# ADC_part3.net
KiCad netlist of a schematic drawn in Altium Designer
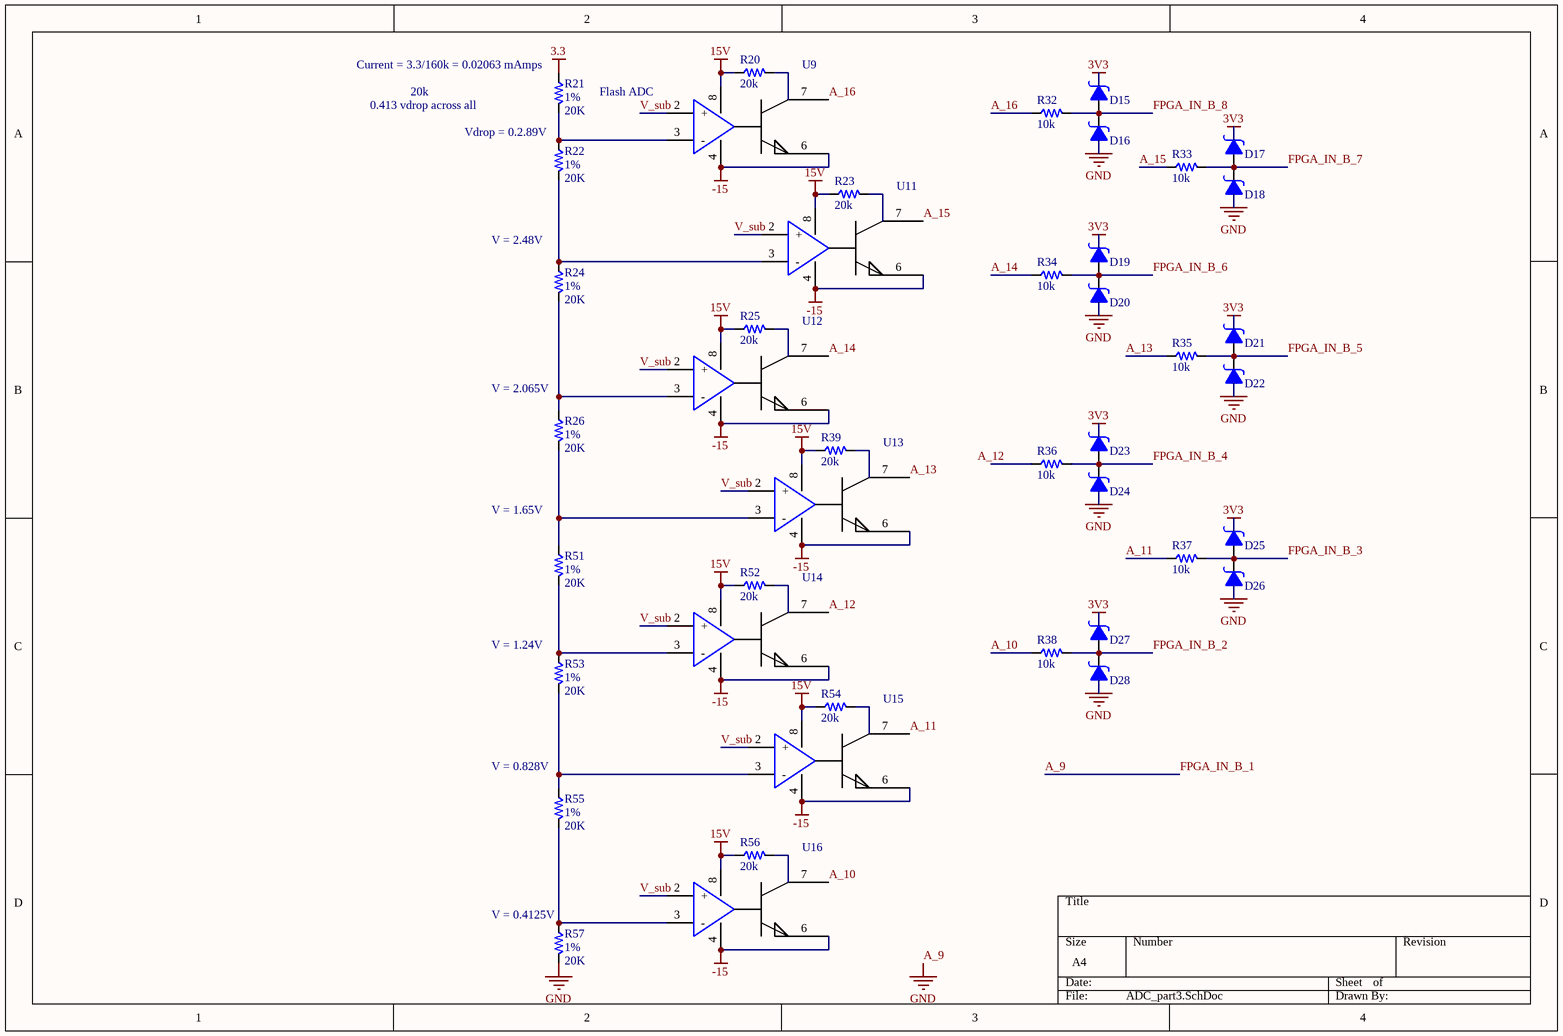
[diagram p0: ADC_part3.SchDoc]

(export (version "E")
  (design (tool "Eeschema 10.0.6"))
  (components
    (comp (ref "D15")
      (value "ONSEMI_MBRM110LT1G")
      (footprint "ON Semi Schottky Diode - MBRM110LT1G")
      (description "DIODE SCHOTTKY 10V 1A")
      (libsource (lib "ON Semi Schottky Diode") (part "ONSEMI_MBRM110LT1G"))
    )
    (comp (ref "D16")
      (value "ONSEMI_MBRM110LT1G")
      (footprint "ON Semi Schottky Diode - MBRM110LT1G")
      (description "DIODE SCHOTTKY 10V 1A")
      (libsource (lib "ON Semi Schottky Diode") (part "ONSEMI_MBRM110LT1G"))
    )
    (comp (ref "D17")
      (value "ONSEMI_MBRM110LT1G")
      (footprint "ON Semi Schottky Diode - MBRM110LT1G")
      (description "DIODE SCHOTTKY 10V 1A")
      (libsource (lib "ON Semi Schottky Diode") (part "ONSEMI_MBRM110LT1G"))
    )
    (comp (ref "D18")
      (value "ONSEMI_MBRM110LT1G")
      (footprint "ON Semi Schottky Diode - MBRM110LT1G")
      (description "DIODE SCHOTTKY 10V 1A")
      (libsource (lib "ON Semi Schottky Diode") (part "ONSEMI_MBRM110LT1G"))
    )
    (comp (ref "D19")
      (value "ONSEMI_MBRM110LT1G")
      (footprint "ON Semi Schottky Diode - MBRM110LT1G")
      (description "DIODE SCHOTTKY 10V 1A")
      (libsource (lib "ON Semi Schottky Diode") (part "ONSEMI_MBRM110LT1G"))
    )
    (comp (ref "D20")
      (value "ONSEMI_MBRM110LT1G")
      (footprint "ON Semi Schottky Diode - MBRM110LT1G")
      (description "DIODE SCHOTTKY 10V 1A")
      (libsource (lib "ON Semi Schottky Diode") (part "ONSEMI_MBRM110LT1G"))
    )
    (comp (ref "D21")
      (value "ONSEMI_MBRM110LT1G")
      (footprint "ON Semi Schottky Diode - MBRM110LT1G")
      (description "DIODE SCHOTTKY 10V 1A")
      (libsource (lib "ON Semi Schottky Diode") (part "ONSEMI_MBRM110LT1G"))
    )
    (comp (ref "D22")
      (value "ONSEMI_MBRM110LT1G")
      (footprint "ON Semi Schottky Diode - MBRM110LT1G")
      (description "DIODE SCHOTTKY 10V 1A")
      (libsource (lib "ON Semi Schottky Diode") (part "ONSEMI_MBRM110LT1G"))
    )
    (comp (ref "D23")
      (value "ONSEMI_MBRM110LT1G")
      (footprint "ON Semi Schottky Diode - MBRM110LT1G")
      (description "DIODE SCHOTTKY 10V 1A")
      (libsource (lib "ON Semi Schottky Diode") (part "ONSEMI_MBRM110LT1G"))
    )
    (comp (ref "D24")
      (value "ONSEMI_MBRM110LT1G")
      (footprint "ON Semi Schottky Diode - MBRM110LT1G")
      (description "DIODE SCHOTTKY 10V 1A")
      (libsource (lib "ON Semi Schottky Diode") (part "ONSEMI_MBRM110LT1G"))
    )
    (comp (ref "D25")
      (value "ONSEMI_MBRM110LT1G")
      (footprint "ON Semi Schottky Diode - MBRM110LT1G")
      (description "DIODE SCHOTTKY 10V 1A")
      (libsource (lib "ON Semi Schottky Diode") (part "ONSEMI_MBRM110LT1G"))
    )
    (comp (ref "D26")
      (value "ONSEMI_MBRM110LT1G")
      (footprint "ON Semi Schottky Diode - MBRM110LT1G")
      (description "DIODE SCHOTTKY 10V 1A")
      (libsource (lib "ON Semi Schottky Diode") (part "ONSEMI_MBRM110LT1G"))
    )
    (comp (ref "D27")
      (value "ONSEMI_MBRM110LT1G")
      (footprint "ON Semi Schottky Diode - MBRM110LT1G")
      (description "DIODE SCHOTTKY 10V 1A")
      (libsource (lib "ON Semi Schottky Diode") (part "ONSEMI_MBRM110LT1G"))
    )
    (comp (ref "D28")
      (value "ONSEMI_MBRM110LT1G")
      (footprint "ON Semi Schottky Diode - MBRM110LT1G")
      (description "DIODE SCHOTTKY 10V 1A")
      (libsource (lib "ON Semi Schottky Diode") (part "ONSEMI_MBRM110LT1G"))
    )
    (comp (ref "R20")
      (value "20k")
      (footprint "PCB_GENERIC_SMD_0603")
      (description "RES 0603 100ohm 5% 63mW")
      (fields (field (name "TOLERANCE") "5%") (field (name "POWER") "63mW"))
      (libsource (lib "RES") (part "R060-00101-05"))
    )
    (comp (ref "R21")
      (value "20K")
      (footprint "PCB_GENERIC_SMD_0603")
      (description "RES 0603 10K 1% 100mW")
      (fields
        (field (name "POWER") "100mW")
        (field (name "TOLERANCE") "1%")
        (field (name "Comment") "R060-00103-01")
      )
      (libsource (lib "RES") (part "R060-00103-01"))
    )
    (comp (ref "R22")
      (value "20K")
      (footprint "PCB_GENERIC_SMD_0603")
      (description "RES 0603 10K 1% 100mW")
      (fields
        (field (name "POWER") "100mW")
        (field (name "TOLERANCE") "1%")
        (field (name "Comment") "R060-00103-01")
      )
      (libsource (lib "RES") (part "R060-00103-01"))
    )
    (comp (ref "R23")
      (value "20k")
      (footprint "PCB_GENERIC_SMD_0603")
      (description "RES 0603 100ohm 5% 63mW")
      (fields (field (name "TOLERANCE") "5%") (field (name "POWER") "63mW"))
      (libsource (lib "RES") (part "R060-00101-05"))
    )
    (comp (ref "R24")
      (value "20K")
      (footprint "PCB_GENERIC_SMD_0603")
      (description "RES 0603 10K 1% 100mW")
      (fields
        (field (name "POWER") "100mW")
        (field (name "TOLERANCE") "1%")
        (field (name "Comment") "R060-00103-01")
      )
      (libsource (lib "RES") (part "R060-00103-01"))
    )
    (comp (ref "R25")
      (value "20k")
      (footprint "PCB_GENERIC_SMD_0603")
      (description "RES 0603 100ohm 5% 63mW")
      (fields (field (name "TOLERANCE") "5%") (field (name "POWER") "63mW"))
      (libsource (lib "RES") (part "R060-00101-05"))
    )
    (comp (ref "R26")
      (value "20K")
      (footprint "PCB_GENERIC_SMD_0603")
      (description "RES 0603 10K 1% 100mW")
      (fields
        (field (name "POWER") "100mW")
        (field (name "TOLERANCE") "1%")
        (field (name "Comment") "R060-00103-01")
      )
      (libsource (lib "RES") (part "R060-00103-01"))
    )
    (comp (ref "R32")
      (value "10k")
      (footprint "PCB_GENERIC_SMD_0603")
      (description "RES 0603 100ohm 5% 63mW")
      (fields (field (name "TOLERANCE") "5%") (field (name "POWER") "63mW"))
      (libsource (lib "RES") (part "R060-00101-05"))
    )
    (comp (ref "R33")
      (value "10k")
      (footprint "PCB_GENERIC_SMD_0603")
      (description "RES 0603 100ohm 5% 63mW")
      (fields (field (name "TOLERANCE") "5%") (field (name "POWER") "63mW"))
      (libsource (lib "RES") (part "R060-00101-05"))
    )
    (comp (ref "R34")
      (value "10k")
      (footprint "PCB_GENERIC_SMD_0603")
      (description "RES 0603 100ohm 5% 63mW")
      (fields (field (name "TOLERANCE") "5%") (field (name "POWER") "63mW"))
      (libsource (lib "RES") (part "R060-00101-05"))
    )
    (comp (ref "R35")
      (value "10k")
      (footprint "PCB_GENERIC_SMD_0603")
      (description "RES 0603 100ohm 5% 63mW")
      (fields (field (name "TOLERANCE") "5%") (field (name "POWER") "63mW"))
      (libsource (lib "RES") (part "R060-00101-05"))
    )
    (comp (ref "R36")
      (value "10k")
      (footprint "PCB_GENERIC_SMD_0603")
      (description "RES 0603 100ohm 5% 63mW")
      (fields (field (name "TOLERANCE") "5%") (field (name "POWER") "63mW"))
      (libsource (lib "RES") (part "R060-00101-05"))
    )
    (comp (ref "R37")
      (value "10k")
      (footprint "PCB_GENERIC_SMD_0603")
      (description "RES 0603 100ohm 5% 63mW")
      (fields (field (name "TOLERANCE") "5%") (field (name "POWER") "63mW"))
      (libsource (lib "RES") (part "R060-00101-05"))
    )
    (comp (ref "R38")
      (value "10k")
      (footprint "PCB_GENERIC_SMD_0603")
      (description "RES 0603 100ohm 5% 63mW")
      (fields (field (name "TOLERANCE") "5%") (field (name "POWER") "63mW"))
      (libsource (lib "RES") (part "R060-00101-05"))
    )
    (comp (ref "R39")
      (value "20k")
      (footprint "PCB_GENERIC_SMD_0603")
      (description "RES 0603 100ohm 5% 63mW")
      (fields (field (name "TOLERANCE") "5%") (field (name "POWER") "63mW"))
      (libsource (lib "RES") (part "R060-00101-05"))
    )
    (comp (ref "R51")
      (value "20K")
      (footprint "PCB_GENERIC_SMD_0603")
      (description "RES 0603 10K 1% 100mW")
      (fields
        (field (name "POWER") "100mW")
        (field (name "TOLERANCE") "1%")
        (field (name "Comment") "R060-00103-01")
      )
      (libsource (lib "RES") (part "R060-00103-01"))
    )
    (comp (ref "R52")
      (value "20k")
      (footprint "PCB_GENERIC_SMD_0603")
      (description "RES 0603 100ohm 5% 63mW")
      (fields (field (name "TOLERANCE") "5%") (field (name "POWER") "63mW"))
      (libsource (lib "RES") (part "R060-00101-05"))
    )
    (comp (ref "R53")
      (value "20K")
      (footprint "PCB_GENERIC_SMD_0603")
      (description "RES 0603 10K 1% 100mW")
      (fields
        (field (name "POWER") "100mW")
        (field (name "TOLERANCE") "1%")
        (field (name "Comment") "R060-00103-01")
      )
      (libsource (lib "RES") (part "R060-00103-01"))
    )
    (comp (ref "R54")
      (value "20k")
      (footprint "PCB_GENERIC_SMD_0603")
      (description "RES 0603 100ohm 5% 63mW")
      (fields (field (name "TOLERANCE") "5%") (field (name "POWER") "63mW"))
      (libsource (lib "RES") (part "R060-00101-05"))
    )
    (comp (ref "R55")
      (value "20K")
      (footprint "PCB_GENERIC_SMD_0603")
      (description "RES 0603 10K 1% 100mW")
      (fields
        (field (name "POWER") "100mW")
        (field (name "TOLERANCE") "1%")
        (field (name "Comment") "R060-00103-01")
      )
      (libsource (lib "RES") (part "R060-00103-01"))
    )
    (comp (ref "R56")
      (value "20k")
      (footprint "PCB_GENERIC_SMD_0603")
      (description "RES 0603 100ohm 5% 63mW")
      (fields (field (name "TOLERANCE") "5%") (field (name "POWER") "63mW"))
      (libsource (lib "RES") (part "R060-00101-05"))
    )
    (comp (ref "R57")
      (value "20K")
      (footprint "PCB_GENERIC_SMD_0603")
      (description "RES 0603 10K 1% 100mW")
      (fields
        (field (name "POWER") "100mW")
        (field (name "TOLERANCE") "1%")
        (field (name "Comment") "R060-00103-01")
      )
      (libsource (lib "RES") (part "R060-00103-01"))
    )
    (comp (ref "U9")
      (value "AP331A")
      (footprint "SOT95P285X130-5N")
      (description "Single Channel Comparator, Open Drain, SC-74A/SOT-753")
      (libsource (lib "Comparator") (part "AP331A"))
    )
    (comp (ref "U11")
      (value "AP331A")
      (footprint "SOT95P285X130-5N")
      (description "Single Channel Comparator, Open Drain, SC-74A/SOT-753")
      (libsource (lib "Comparator") (part "AP331A"))
    )
    (comp (ref "U12")
      (value "AP331A")
      (footprint "SOT95P285X130-5N")
      (description "Single Channel Comparator, Open Drain, SC-74A/SOT-753")
      (libsource (lib "Comparator") (part "AP331A"))
    )
    (comp (ref "U13")
      (value "AP331A")
      (footprint "SOT95P285X130-5N")
      (description "Single Channel Comparator, Open Drain, SC-74A/SOT-753")
      (libsource (lib "Comparator") (part "AP331A"))
    )
    (comp (ref "U14")
      (value "AP331A")
      (footprint "SOT95P285X130-5N")
      (description "Single Channel Comparator, Open Drain, SC-74A/SOT-753")
      (libsource (lib "Comparator") (part "AP331A"))
    )
    (comp (ref "U15")
      (value "AP331A")
      (footprint "SOT95P285X130-5N")
      (description "Single Channel Comparator, Open Drain, SC-74A/SOT-753")
      (libsource (lib "Comparator") (part "AP331A"))
    )
    (comp (ref "U16")
      (value "AP331A")
      (footprint "SOT95P285X130-5N")
      (description "Single Channel Comparator, Open Drain, SC-74A/SOT-753")
      (libsource (lib "Comparator") (part "AP331A"))
    )
  )
  (nets
    (net (code "1") (name "-15") (class "Default")
      (node (ref "U11") (pin "4") (pinfunction "GND_4") (pintype "passive"))
      (node (ref "U11") (pin "6") (pinfunction "10_6") (pintype "passive"))
      (node (ref "U12") (pin "4") (pinfunction "GND_4") (pintype "passive"))
      (node (ref "U12") (pin "6") (pinfunction "10_6") (pintype "passive"))
      (node (ref "U13") (pin "4") (pinfunction "GND_4") (pintype "passive"))
      (node (ref "U13") (pin "6") (pinfunction "10_6") (pintype "passive"))
      (node (ref "U14") (pin "4") (pinfunction "GND_4") (pintype "passive"))
      (node (ref "U14") (pin "6") (pinfunction "10_6") (pintype "passive"))
      (node (ref "U15") (pin "4") (pinfunction "GND_4") (pintype "passive"))
      (node (ref "U15") (pin "6") (pinfunction "10_6") (pintype "passive"))
      (node (ref "U16") (pin "4") (pinfunction "GND_4") (pintype "passive"))
      (node (ref "U16") (pin "6") (pinfunction "10_6") (pintype "passive"))
      (node (ref "U9") (pin "4") (pinfunction "GND_4") (pintype "passive"))
      (node (ref "U9") (pin "6") (pinfunction "10_6") (pintype "passive"))
    )
    (net (code "2") (name "/A_10") (class "Default")
      (node (ref "R38") (pin "1") (pinfunction "1_1") (pintype "passive"))
      (node (ref "U16") (pin "7") (pinfunction "9_7") (pintype "passive"))
    )
    (net (code "3") (name "/A_11") (class "Default")
      (node (ref "R37") (pin "1") (pinfunction "1_1") (pintype "passive"))
      (node (ref "U15") (pin "7") (pinfunction "9_7") (pintype "passive"))
    )
    (net (code "4") (name "/A_12") (class "Default")
      (node (ref "U14") (pin "7") (pinfunction "9_7") (pintype "passive"))
    )
    (net (code "5") (name "/A_13") (class "Default")
      (node (ref "R35") (pin "1") (pinfunction "1_1") (pintype "passive"))
      (node (ref "U13") (pin "7") (pinfunction "9_7") (pintype "passive"))
    )
    (net (code "6") (name "/A_14") (class "Default")
      (node (ref "R34") (pin "1") (pinfunction "1_1") (pintype "passive"))
      (node (ref "U12") (pin "7") (pinfunction "9_7") (pintype "passive"))
    )
    (net (code "7") (name "/A_15") (class "Default")
      (node (ref "R33") (pin "1") (pinfunction "1_1") (pintype "passive"))
      (node (ref "U11") (pin "7") (pinfunction "9_7") (pintype "passive"))
    )
    (net (code "8") (name "/A_16") (class "Default")
      (node (ref "R32") (pin "1") (pinfunction "1_1") (pintype "passive"))
      (node (ref "U9") (pin "7") (pinfunction "9_7") (pintype "passive"))
    )
    (net (code "9") (name "/FPGA_IN_B_2") (class "Default")
      (node (ref "D27") (pin "2") (pinfunction "2_2") (pintype "passive"))
      (node (ref "D28") (pin "1") (pinfunction "1_1") (pintype "passive"))
      (node (ref "R38") (pin "2") (pinfunction "2_2") (pintype "passive"))
    )
    (net (code "10") (name "/FPGA_IN_B_3") (class "Default")
      (node (ref "D25") (pin "2") (pinfunction "2_2") (pintype "passive"))
      (node (ref "D26") (pin "1") (pinfunction "1_1") (pintype "passive"))
      (node (ref "R37") (pin "2") (pinfunction "2_2") (pintype "passive"))
    )
    (net (code "11") (name "/FPGA_IN_B_4") (class "Default")
      (node (ref "D23") (pin "2") (pinfunction "2_2") (pintype "passive"))
      (node (ref "D24") (pin "1") (pinfunction "1_1") (pintype "passive"))
      (node (ref "R36") (pin "2") (pinfunction "2_2") (pintype "passive"))
    )
    (net (code "12") (name "/FPGA_IN_B_5") (class "Default")
      (node (ref "D21") (pin "2") (pinfunction "2_2") (pintype "passive"))
      (node (ref "D22") (pin "1") (pinfunction "1_1") (pintype "passive"))
      (node (ref "R35") (pin "2") (pinfunction "2_2") (pintype "passive"))
    )
    (net (code "13") (name "/FPGA_IN_B_6") (class "Default")
      (node (ref "D19") (pin "2") (pinfunction "2_2") (pintype "passive"))
      (node (ref "D20") (pin "1") (pinfunction "1_1") (pintype "passive"))
      (node (ref "R34") (pin "2") (pinfunction "2_2") (pintype "passive"))
    )
    (net (code "14") (name "/FPGA_IN_B_7") (class "Default")
      (node (ref "D17") (pin "2") (pinfunction "2_2") (pintype "passive"))
      (node (ref "D18") (pin "1") (pinfunction "1_1") (pintype "passive"))
      (node (ref "R33") (pin "2") (pinfunction "2_2") (pintype "passive"))
    )
    (net (code "15") (name "/FPGA_IN_B_8") (class "Default")
      (node (ref "D15") (pin "2") (pinfunction "2_2") (pintype "passive"))
      (node (ref "D16") (pin "1") (pinfunction "1_1") (pintype "passive"))
      (node (ref "R32") (pin "2") (pinfunction "2_2") (pintype "passive"))
    )
    (net (code "16") (name "/V_sub") (class "Default")
      (node (ref "U11") (pin "2") (pinfunction "+_2") (pintype "passive"))
      (node (ref "U12") (pin "2") (pinfunction "+_2") (pintype "passive"))
      (node (ref "U13") (pin "2") (pinfunction "+_2") (pintype "passive"))
      (node (ref "U14") (pin "2") (pinfunction "+_2") (pintype "passive"))
      (node (ref "U15") (pin "2") (pinfunction "+_2") (pintype "passive"))
      (node (ref "U16") (pin "2") (pinfunction "+_2") (pintype "passive"))
      (node (ref "U9") (pin "2") (pinfunction "+_2") (pintype "passive"))
    )
    (net (code "17") (name "3.3") (class "Default")
      (node (ref "R21") (pin "1") (pinfunction "1_1") (pintype "passive"))
    )
    (net (code "18") (name "3V3") (class "Default")
      (node (ref "D15") (pin "1") (pinfunction "1_1") (pintype "passive"))
      (node (ref "D17") (pin "1") (pinfunction "1_1") (pintype "passive"))
      (node (ref "D19") (pin "1") (pinfunction "1_1") (pintype "passive"))
      (node (ref "D21") (pin "1") (pinfunction "1_1") (pintype "passive"))
      (node (ref "D23") (pin "1") (pinfunction "1_1") (pintype "passive"))
      (node (ref "D25") (pin "1") (pinfunction "1_1") (pintype "passive"))
      (node (ref "D27") (pin "1") (pinfunction "1_1") (pintype "passive"))
    )
    (net (code "19") (name "15V") (class "Default")
      (node (ref "R20") (pin "1") (pinfunction "1_1") (pintype "passive"))
      (node (ref "R23") (pin "1") (pinfunction "1_1") (pintype "passive"))
      (node (ref "R25") (pin "1") (pinfunction "1_1") (pintype "passive"))
      (node (ref "R39") (pin "1") (pinfunction "1_1") (pintype "passive"))
      (node (ref "R52") (pin "1") (pinfunction "1_1") (pintype "passive"))
      (node (ref "R54") (pin "1") (pinfunction "1_1") (pintype "passive"))
      (node (ref "R56") (pin "1") (pinfunction "1_1") (pintype "passive"))
      (node (ref "U11") (pin "8") (pinfunction "VCC_8") (pintype "passive"))
      (node (ref "U12") (pin "8") (pinfunction "VCC_8") (pintype "passive"))
      (node (ref "U13") (pin "8") (pinfunction "VCC_8") (pintype "passive"))
      (node (ref "U14") (pin "8") (pinfunction "VCC_8") (pintype "passive"))
      (node (ref "U15") (pin "8") (pinfunction "VCC_8") (pintype "passive"))
      (node (ref "U16") (pin "8") (pinfunction "VCC_8") (pintype "passive"))
      (node (ref "U9") (pin "8") (pinfunction "VCC_8") (pintype "passive"))
    )
    (net (code "20") (name "GND") (class "Default")
      (node (ref "D16") (pin "2") (pinfunction "2_2") (pintype "passive"))
      (node (ref "D18") (pin "2") (pinfunction "2_2") (pintype "passive"))
      (node (ref "D20") (pin "2") (pinfunction "2_2") (pintype "passive"))
      (node (ref "D22") (pin "2") (pinfunction "2_2") (pintype "passive"))
      (node (ref "D24") (pin "2") (pinfunction "2_2") (pintype "passive"))
      (node (ref "D26") (pin "2") (pinfunction "2_2") (pintype "passive"))
      (node (ref "D28") (pin "2") (pinfunction "2_2") (pintype "passive"))
      (node (ref "R57") (pin "2") (pinfunction "2_2") (pintype "passive"))
    )
    (net (code "21") (name "Net-(U9--)") (class "Default")
      (node (ref "R21") (pin "2") (pinfunction "2_2") (pintype "passive"))
      (node (ref "R22") (pin "1") (pinfunction "1_1") (pintype "passive"))
      (node (ref "U9") (pin "3") (pinfunction "-_3") (pintype "passive"))
    )
    (net (code "22") (name "Net-(U11--)") (class "Default")
      (node (ref "R22") (pin "2") (pinfunction "2_2") (pintype "passive"))
      (node (ref "R24") (pin "1") (pinfunction "1_1") (pintype "passive"))
      (node (ref "U11") (pin "3") (pinfunction "-_3") (pintype "passive"))
    )
    (net (code "23") (name "Net-(U12--)") (class "Default")
      (node (ref "R24") (pin "2") (pinfunction "2_2") (pintype "passive"))
      (node (ref "R26") (pin "1") (pinfunction "1_1") (pintype "passive"))
      (node (ref "U12") (pin "3") (pinfunction "-_3") (pintype "passive"))
    )
    (net (code "24") (name "Net-(U13--)") (class "Default")
      (node (ref "R26") (pin "2") (pinfunction "2_2") (pintype "passive"))
      (node (ref "R51") (pin "1") (pinfunction "1_1") (pintype "passive"))
      (node (ref "U13") (pin "3") (pinfunction "-_3") (pintype "passive"))
    )
    (net (code "25") (name "Net-(U14--)") (class "Default")
      (node (ref "R51") (pin "2") (pinfunction "2_2") (pintype "passive"))
      (node (ref "R53") (pin "1") (pinfunction "1_1") (pintype "passive"))
      (node (ref "U14") (pin "3") (pinfunction "-_3") (pintype "passive"))
    )
    (net (code "26") (name "Net-(U15--)") (class "Default")
      (node (ref "R53") (pin "2") (pinfunction "2_2") (pintype "passive"))
      (node (ref "R55") (pin "1") (pinfunction "1_1") (pintype "passive"))
      (node (ref "U15") (pin "3") (pinfunction "-_3") (pintype "passive"))
    )
    (net (code "27") (name "Net-(U16--)") (class "Default")
      (node (ref "R55") (pin "2") (pinfunction "2_2") (pintype "passive"))
      (node (ref "R57") (pin "1") (pinfunction "1_1") (pintype "passive"))
      (node (ref "U16") (pin "3") (pinfunction "-_3") (pintype "passive"))
    )
    (net (code "28") (name "unconnected-(R20-Pad2)") (class "Default")
      (node (ref "R20") (pin "2") (pinfunction "2_2") (pintype "passive"))
    )
    (net (code "29") (name "unconnected-(R23-Pad2)") (class "Default")
      (node (ref "R23") (pin "2") (pinfunction "2_2") (pintype "passive"))
    )
    (net (code "30") (name "unconnected-(R25-Pad2)") (class "Default")
      (node (ref "R25") (pin "2") (pinfunction "2_2") (pintype "passive"))
    )
    (net (code "31") (name "unconnected-(R36-Pad1)") (class "Default")
      (node (ref "R36") (pin "1") (pinfunction "1_1") (pintype "passive"))
    )
    (net (code "32") (name "unconnected-(R39-Pad2)") (class "Default")
      (node (ref "R39") (pin "2") (pinfunction "2_2") (pintype "passive"))
    )
    (net (code "33") (name "unconnected-(R52-Pad2)") (class "Default")
      (node (ref "R52") (pin "2") (pinfunction "2_2") (pintype "passive"))
    )
    (net (code "34") (name "unconnected-(R54-Pad2)") (class "Default")
      (node (ref "R54") (pin "2") (pinfunction "2_2") (pintype "passive"))
    )
    (net (code "35") (name "unconnected-(R56-Pad2)") (class "Default")
      (node (ref "R56") (pin "2") (pinfunction "2_2") (pintype "passive"))
    )
  )
)
